# schematic.net
KiCad netlist of a schematic drawn in EAGLE
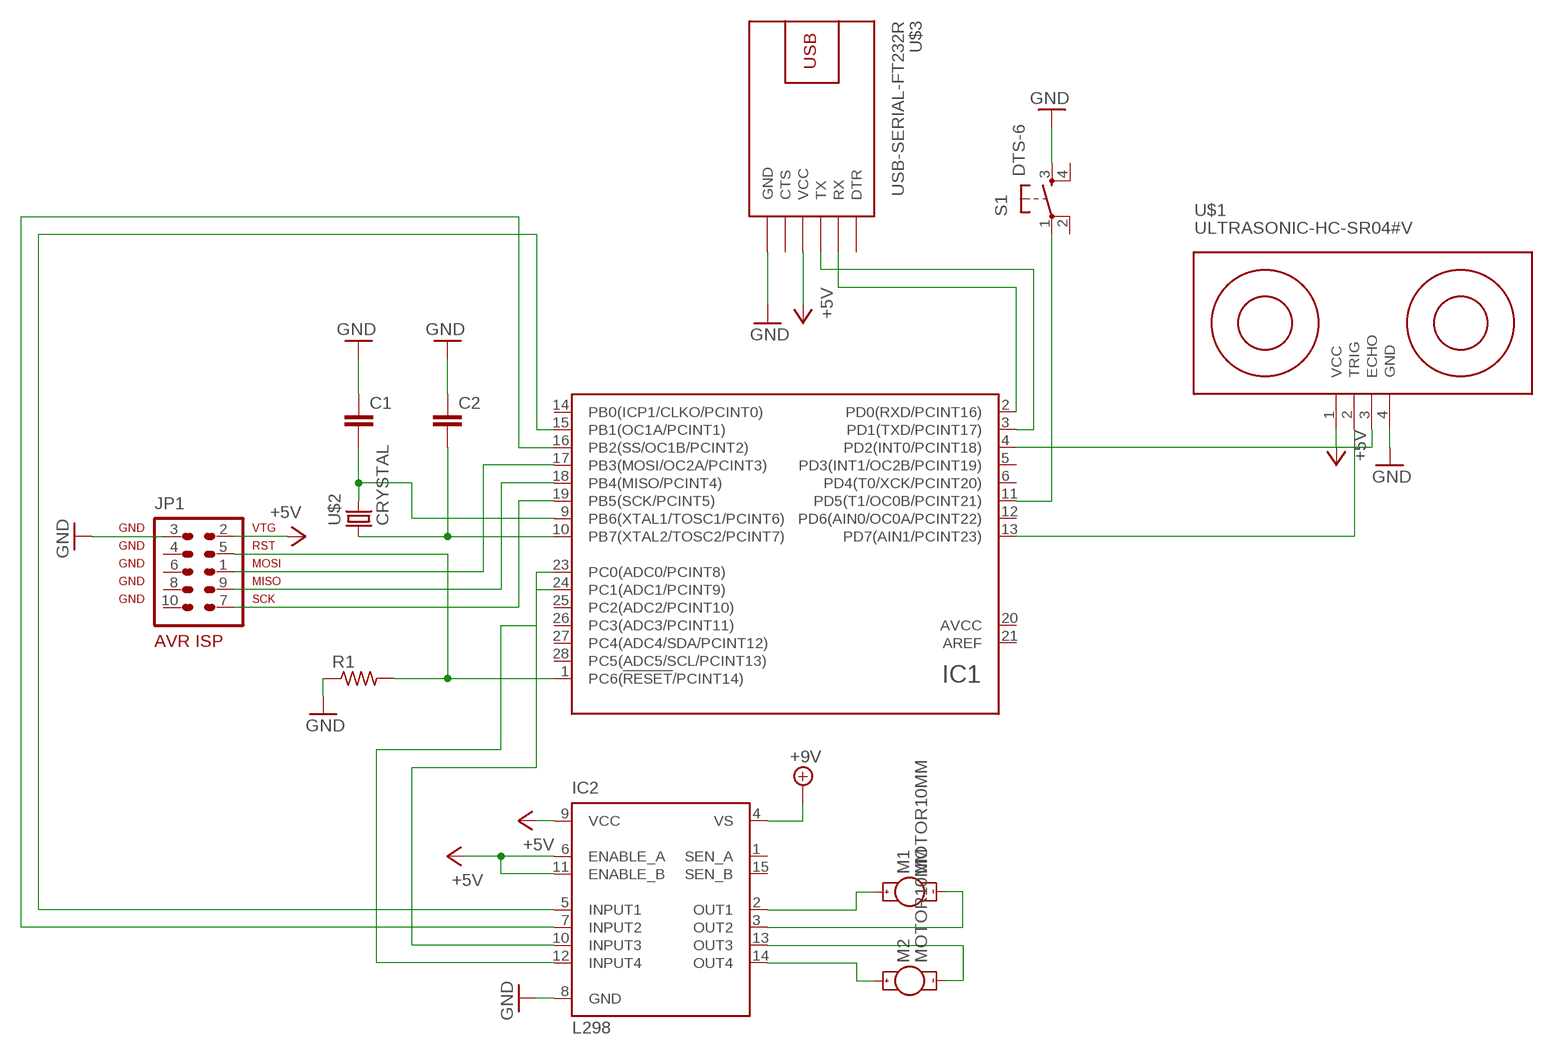
[diagram p0: schematic, sheet 1]

(export (version "E")
  (design (tool "Eeschema 10.0.6"))
  (components
    (comp (ref "C1")
      (value "C-EU025-024X044")
      (footprint "eagle-import:C025-024X044")
      (libsource (lib "eagle-import") (part "C-EU025-024X044"))
    )
    (comp (ref "C2")
      (value "C-EU025-024X044")
      (footprint "eagle-import:C025-024X044")
      (libsource (lib "eagle-import") (part "C-EU025-024X044"))
    )
    (comp (ref "IC1")
      (value "ATMEGA48/88/168/328-PU(DIP28)PU")
      (footprint "eagle-import:DIL28")
      (libsource (lib "eagle-import") (part "ATMEGA48/88/168/328-PU(DIP28)PU"))
    )
    (comp (ref "IC2")
      (value "L298")
      (footprint "eagle-import:MULTIWATT-15")
      (fields (field (name "MPN") "L298N"))
      (libsource (lib "eagle-import") (part "L298"))
    )
    (comp (ref "JP1")
      (value "AVR-ISP-10")
      (footprint "eagle-import:AVR-ISP-10")
      (libsource (lib "eagle-import") (part "AVR-ISP-10"))
    )
    (comp (ref "M1")
      (value "MOTOR10MM")
      (footprint "eagle-import:VIBE-MOTOR-10MM")
      (libsource (lib "eagle-import") (part "MOTOR10MM"))
    )
    (comp (ref "M2")
      (value "MOTOR10MM")
      (footprint "eagle-import:VIBE-MOTOR-10MM")
      (libsource (lib "eagle-import") (part "MOTOR10MM"))
    )
    (comp (ref "R1")
      (value "R-US_0204/5")
      (footprint "eagle-import:0204_5")
      (libsource (lib "eagle-import") (part "R-US_0204/5"))
    )
    (comp (ref "S1")
      (value "DTS-6")
      (footprint "eagle-import:DTS-6")
      (libsource (lib "eagle-import") (part "DTS-6"))
    )
    (comp (ref "U$1")
      (value "ULTRASONIC-HC-SR04#V")
      (footprint "eagle-import:ULTRASONIC-HC-SR04#V")
      (libsource (lib "eagle-import") (part "ULTRASONIC-HC-SR04#V"))
    )
    (comp (ref "U$2")
      (value "CRYSTAL")
      (footprint "eagle-import:2-SMD-5X3MM")
      (libsource (lib "eagle-import") (part "CRYSTAL"))
    )
    (comp (ref "U$3")
      (value "USB-SERIAL-FT232R")
      (footprint "eagle-import:USB-SERIAL-FT232R")
      (libsource (lib "eagle-import") (part "USB-SERIAL-FT232R"))
    )
  )
  (nets
    (net (code "1") (name "+5V") (class "Default")
      (node (ref "IC2") (pin "11") (pinfunction "ENABLE_B_11") (pintype "input"))
      (node (ref "IC2") (pin "6") (pinfunction "ENABLE_A_6") (pintype "input"))
      (node (ref "IC2") (pin "9") (pinfunction "VCC_9") (pintype "power_in"))
      (node (ref "JP1") (pin "2") (pinfunction "2_2") (pintype "passive"))
      (node (ref "U$1") (pin "1") (pinfunction "VCC_1") (pintype "power_in"))
      (node (ref "U$3") (pin "4") (pinfunction "VCC_4") (pintype "power_in"))
    )
    (net (code "2") (name "+9V") (class "Default")
      (node (ref "IC2") (pin "4") (pinfunction "VS_4") (pintype "power_in"))
    )
    (net (code "3") (name "/AVCC") (class "Default")
      (node (ref "IC1") (pin "20") (pinfunction "AVCC_20") (pintype "power_in"))
    )
    (net (code "4") (name "GND") (class "Default")
      (node (ref "C1") (pin "1") (pinfunction "1_1") (pintype "passive"))
      (node (ref "C2") (pin "1") (pinfunction "1_1") (pintype "passive"))
      (node (ref "IC2") (pin "8") (pinfunction "GND_8") (pintype "power_in"))
      (node (ref "JP1") (pin "3") (pinfunction "3_3") (pintype "passive"))
      (node (ref "R1") (pin "1") (pinfunction "1_1") (pintype "passive"))
      (node (ref "S1") (pin "3") (pinfunction "3_3") (pintype "passive"))
      (node (ref "U$1") (pin "4") (pinfunction "GND_4") (pintype "power_in"))
      (node (ref "U$3") (pin "6") (pinfunction "GND_6") (pintype "bidirectional"))
    )
    (net (code "5") (name "Net-(IC1A-PB1(OC1A{slash}PCINT1))") (class "Default")
      (node (ref "IC1") (pin "15") (pinfunction "PB1(OC1A/PCINT1)_15") (pintype "bidirectional"))
      (node (ref "IC2") (pin "5") (pinfunction "INPUT1_5") (pintype "input"))
    )
    (net (code "6") (name "Net-(IC1A-PB2(SS{slash}OC1B{slash}PCINT2))") (class "Default")
      (node (ref "IC1") (pin "16") (pinfunction "PB2(SS/OC1B/PCINT2)_16") (pintype "bidirectional"))
      (node (ref "IC2") (pin "7") (pinfunction "INPUT2_7") (pintype "input"))
    )
    (net (code "7") (name "Net-(IC1A-PB3(MOSI{slash}OC2A{slash}PCINT3))") (class "Default")
      (node (ref "IC1") (pin "17") (pinfunction "PB3(MOSI/OC2A/PCINT3)_17") (pintype "bidirectional"))
      (node (ref "JP1") (pin "1") (pinfunction "1_1") (pintype "passive"))
    )
    (net (code "8") (name "Net-(IC1A-PB4(MISO{slash}PCINT4))") (class "Default")
      (node (ref "IC1") (pin "18") (pinfunction "PB4(MISO/PCINT4)_18") (pintype "bidirectional"))
      (node (ref "JP1") (pin "9") (pinfunction "9_9") (pintype "passive"))
    )
    (net (code "9") (name "Net-(IC1A-PB5(SCK{slash}PCINT5))") (class "Default")
      (node (ref "IC1") (pin "19") (pinfunction "PB5(SCK/PCINT5)_19") (pintype "bidirectional"))
      (node (ref "JP1") (pin "7") (pinfunction "7_7") (pintype "passive"))
    )
    (net (code "10") (name "Net-(IC1A-PB6(XTAL1{slash}TOSC1{slash}PCINT6))") (class "Default")
      (node (ref "C1") (pin "2") (pinfunction "2_2") (pintype "passive"))
      (node (ref "IC1") (pin "9") (pinfunction "PB6(XTAL1/TOSC1/PCINT6)_9") (pintype "bidirectional"))
      (node (ref "U$2") (pin "P$2") (pinfunction "2_P$2") (pintype "passive"))
    )
    (net (code "11") (name "Net-(IC1A-PB7(XTAL2{slash}TOSC2{slash}PCINT7))") (class "Default")
      (node (ref "C2") (pin "2") (pinfunction "2_2") (pintype "passive"))
      (node (ref "IC1") (pin "10") (pinfunction "PB7(XTAL2/TOSC2/PCINT7)_10") (pintype "bidirectional"))
      (node (ref "U$2") (pin "P$1") (pinfunction "1_P$1") (pintype "passive"))
    )
    (net (code "12") (name "Net-(IC1A-PC0(ADC0{slash}PCINT8))") (class "Default")
      (node (ref "IC1") (pin "23") (pinfunction "PC0(ADC0/PCINT8)_23") (pintype "bidirectional"))
      (node (ref "IC2") (pin "12") (pinfunction "INPUT4_12") (pintype "input"))
    )
    (net (code "13") (name "Net-(IC1A-PC1(ADC1{slash}PCINT9))") (class "Default")
      (node (ref "IC1") (pin "24") (pinfunction "PC1(ADC1/PCINT9)_24") (pintype "bidirectional"))
      (node (ref "IC2") (pin "10") (pinfunction "INPUT3_10") (pintype "input"))
    )
    (net (code "14") (name "Net-(IC1A-PC6(~{RESET}{slash}PCINT14))") (class "Default")
      (node (ref "IC1") (pin "1") (pinfunction "PC6(~{RESET}/PCINT14)_1") (pintype "bidirectional"))
      (node (ref "JP1") (pin "5") (pinfunction "5_5") (pintype "passive"))
      (node (ref "R1") (pin "2") (pinfunction "2_2") (pintype "passive"))
    )
    (net (code "15") (name "Net-(IC1A-PD0(RXD{slash}PCINT16))") (class "Default")
      (node (ref "IC1") (pin "2") (pinfunction "PD0(RXD/PCINT16)_2") (pintype "bidirectional"))
      (node (ref "U$3") (pin "2") (pinfunction "RX_2") (pintype "bidirectional"))
    )
    (net (code "16") (name "Net-(IC1A-PD1(TXD{slash}PCINT17))") (class "Default")
      (node (ref "IC1") (pin "3") (pinfunction "PD1(TXD/PCINT17)_3") (pintype "bidirectional"))
      (node (ref "U$3") (pin "3") (pinfunction "TX_3") (pintype "bidirectional"))
    )
    (net (code "17") (name "Net-(IC1A-PD2(INT0{slash}PCINT18))") (class "Default")
      (node (ref "IC1") (pin "4") (pinfunction "PD2(INT0/PCINT18)_4") (pintype "bidirectional"))
      (node (ref "U$1") (pin "3") (pinfunction "ECHO_3") (pintype "output"))
    )
    (net (code "18") (name "Net-(IC1A-PD5(T1{slash}OC0B{slash}PCINT21))") (class "Default")
      (node (ref "IC1") (pin "11") (pinfunction "PD5(T1/OC0B/PCINT21)_11") (pintype "bidirectional"))
      (node (ref "S1") (pin "1") (pinfunction "1_1") (pintype "passive"))
    )
    (net (code "19") (name "Net-(IC1A-PD7(AIN1{slash}PCINT23))") (class "Default")
      (node (ref "IC1") (pin "13") (pinfunction "PD7(AIN1/PCINT23)_13") (pintype "bidirectional"))
      (node (ref "U$1") (pin "2") (pinfunction "TRIG_2") (pintype "input"))
    )
    (net (code "20") (name "Net-(IC2-OUT1)") (class "Default")
      (node (ref "IC2") (pin "2") (pinfunction "OUT1_2") (pintype "output"))
      (node (ref "M1") (pin "+") (pinfunction "+_+") (pintype "bidirectional"))
    )
    (net (code "21") (name "Net-(IC2-OUT2)") (class "Default")
      (node (ref "IC2") (pin "3") (pinfunction "OUT2_3") (pintype "output"))
      (node (ref "M1") (pin "-") (pinfunction "-_-") (pintype "bidirectional"))
    )
    (net (code "22") (name "Net-(IC2-OUT3)") (class "Default")
      (node (ref "IC2") (pin "13") (pinfunction "OUT3_13") (pintype "output"))
      (node (ref "M2") (pin "-") (pinfunction "-_-") (pintype "bidirectional"))
    )
    (net (code "23") (name "Net-(IC2-OUT4)") (class "Default")
      (node (ref "IC2") (pin "14") (pinfunction "OUT4_14") (pintype "output"))
      (node (ref "M2") (pin "+") (pinfunction "+_+") (pintype "bidirectional"))
    )
    (net (code "24") (name "unconnected-(IC1A-AREF-Pad21)") (class "Default")
      (node (ref "IC1") (pin "21") (pinfunction "AREF_21") (pintype "passive"))
    )
    (net (code "25") (name "unconnected-(IC1A-PB0(ICP1{slash}CLKO{slash}PCINT0)-Pad14)") (class "Default")
      (node (ref "IC1") (pin "14") (pinfunction "PB0(ICP1/CLKO/PCINT0)_14") (pintype "bidirectional"))
    )
    (net (code "26") (name "unconnected-(IC1A-PC2(ADC2{slash}PCINT10)-Pad25)") (class "Default")
      (node (ref "IC1") (pin "25") (pinfunction "PC2(ADC2/PCINT10)_25") (pintype "bidirectional"))
    )
    (net (code "27") (name "unconnected-(IC1A-PC3(ADC3{slash}PCINT11)-Pad26)") (class "Default")
      (node (ref "IC1") (pin "26") (pinfunction "PC3(ADC3/PCINT11)_26") (pintype "bidirectional"))
    )
    (net (code "28") (name "unconnected-(IC1A-PC4(ADC4{slash}SDA{slash}PCINT12)-Pad27)") (class "Default")
      (node (ref "IC1") (pin "27") (pinfunction "PC4(ADC4/SDA/PCINT12)_27") (pintype "bidirectional"))
    )
    (net (code "29") (name "unconnected-(IC1A-PC5(ADC5{slash}SCL{slash}PCINT13)-Pad28)") (class "Default")
      (node (ref "IC1") (pin "28") (pinfunction "PC5(ADC5/SCL/PCINT13)_28") (pintype "bidirectional"))
    )
    (net (code "30") (name "unconnected-(IC1A-PD3(INT1{slash}OC2B{slash}PCINT19)-Pad5)") (class "Default")
      (node (ref "IC1") (pin "5") (pinfunction "PD3(INT1/OC2B/PCINT19)_5") (pintype "bidirectional"))
    )
    (net (code "31") (name "unconnected-(IC1A-PD4(T0{slash}XCK{slash}PCINT20)-Pad6)") (class "Default")
      (node (ref "IC1") (pin "6") (pinfunction "PD4(T0/XCK/PCINT20)_6") (pintype "bidirectional"))
    )
    (net (code "32") (name "unconnected-(IC1A-PD6(AIN0{slash}OC0A{slash}PCINT22)-Pad12)") (class "Default")
      (node (ref "IC1") (pin "12") (pinfunction "PD6(AIN0/OC0A/PCINT22)_12") (pintype "bidirectional"))
    )
    (net (code "33") (name "unconnected-(IC2-SEN_A-Pad1)") (class "Default")
      (node (ref "IC2") (pin "1") (pinfunction "SEN_A_1") (pintype "input"))
    )
    (net (code "34") (name "unconnected-(IC2-SEN_B-Pad15)") (class "Default")
      (node (ref "IC2") (pin "15") (pinfunction "SEN_B_15") (pintype "input"))
    )
    (net (code "35") (name "unconnected-(JP1-Pad4)") (class "Default")
      (node (ref "JP1") (pin "4") (pinfunction "4_4") (pintype "passive"))
    )
    (net (code "36") (name "unconnected-(JP1-Pad6)") (class "Default")
      (node (ref "JP1") (pin "6") (pinfunction "6_6") (pintype "passive"))
    )
    (net (code "37") (name "unconnected-(JP1-Pad8)") (class "Default")
      (node (ref "JP1") (pin "8") (pinfunction "8_8") (pintype "passive"))
    )
    (net (code "38") (name "unconnected-(JP1-Pad10)") (class "Default")
      (node (ref "JP1") (pin "10") (pinfunction "10_10") (pintype "passive"))
    )
    (net (code "39") (name "unconnected-(S1-Pad2)") (class "Default")
      (node (ref "S1") (pin "2") (pinfunction "2_2") (pintype "passive"))
    )
    (net (code "40") (name "unconnected-(S1-Pad4)") (class "Default")
      (node (ref "S1") (pin "4") (pinfunction "4_4") (pintype "passive"))
    )
    (net (code "41") (name "unconnected-(U$3-CTS-Pad5)") (class "Default")
      (node (ref "U$3") (pin "5") (pinfunction "CTS_5") (pintype "bidirectional"))
    )
    (net (code "42") (name "unconnected-(U$3-DTR-Pad1)") (class "Default")
      (node (ref "U$3") (pin "1") (pinfunction "DTR_1") (pintype "bidirectional"))
    )
  )
)
